# Core.net
KiCad netlist of a schematic drawn in Altium Designer
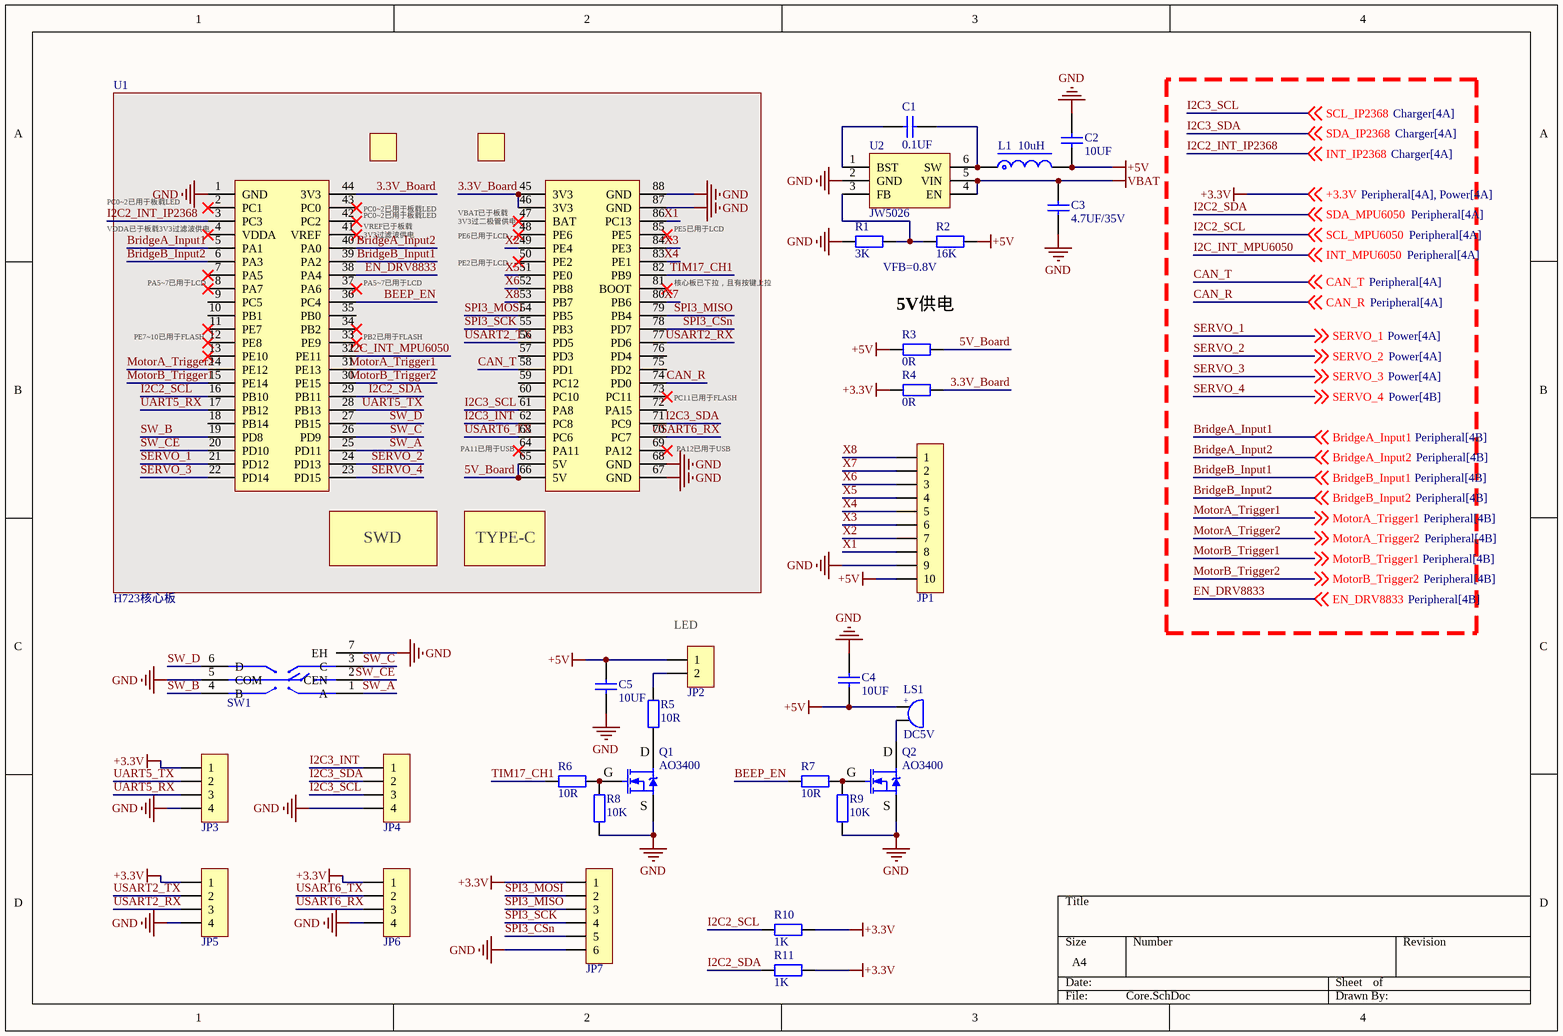
[diagram p0: Core.SchDoc]

(export (version "E")
  (design (tool "Eeschema 10.0.6"))
  (components
    (comp (ref "C1")
      (value "0.1UF")
      (footprint "C0402_NS")
      (description "贴片电容/MLCC电容")
      (libsource (lib "阻容") (part "C"))
    )
    (comp (ref "C2")
      (value "10UF")
      (footprint "C0805_NS")
      (description "贴片电容/MLCC电容")
      (libsource (lib "阻容") (part "C"))
    )
    (comp (ref "C3")
      (value "4.7UF/35V")
      (footprint "C0603_NS")
      (description "贴片电容/MLCC电容")
      (libsource (lib "阻容") (part "C"))
    )
    (comp (ref "C4")
      (value "10UF")
      (footprint "C0805_NS")
      (description "贴片电容/MLCC电容")
      (libsource (lib "阻容") (part "C"))
    )
    (comp (ref "C5")
      (value "10UF")
      (footprint "C0805_NS")
      (description "贴片电容/MLCC电容")
      (libsource (lib "阻容") (part "C"))
    )
    (comp (ref "JP1")
      (value "HDR-1X10")
      (footprint "HDR2.54-WI-10P")
      (description "10P接插件")
      (libsource (lib "2.54mm连接器") (part "Header 10"))
    )
    (comp (ref "JP2")
      (value "HDR-1X2")
      (footprint "XH2.54-WI-2P")
      (description "2P接插件")
      (libsource (lib "2.54mm连接器") (part "Header 2"))
    )
    (comp (ref "JP3")
      (value "HDR-1X4")
      (footprint "XH2.54-WI-4P")
      (description "4P接插件")
      (libsource (lib "2.54mm连接器") (part "Header 4"))
    )
    (comp (ref "JP4")
      (value "HDR-1X4")
      (footprint "XH2.54-WI-4P")
      (description "4P接插件")
      (libsource (lib "2.54mm连接器") (part "Header 4"))
    )
    (comp (ref "JP5")
      (value "HDR-1X4")
      (footprint "XH2.54-WI-4P")
      (description "4P接插件")
      (libsource (lib "2.54mm连接器") (part "Header 4"))
    )
    (comp (ref "JP6")
      (value "HDR-1X4")
      (footprint "HDR2.54-WI-4P")
      (description "4P接插件")
      (libsource (lib "2.54mm连接器") (part "Header 4"))
    )
    (comp (ref "JP7")
      (value "HDR-1X6")
      (footprint "HDR2.54-WI-6P")
      (description "6P接插件")
      (libsource (lib "2.54mm连接器") (part "Header 6"))
    )
    (comp (ref "L1")
      (value "10uH")
      (footprint "L-SMD-0420")
      (description "一体成型电感")
      (libsource (lib "电感") (part "L-Molding Choke"))
    )
    (comp (ref "LS1")
      (value "DC5V")
      (footprint "BEEP 5x9x5.5")
      (description "蜂鸣器")
      (libsource (lib "其他") (part "BEEP"))
    )
    (comp (ref "Q1")
      (value "AO3400")
      (footprint "SOT23-3_L2.9_W1.3_P0.95")
      (description "N沟道 30V/4.2A")
      (libsource (lib "三极管-MOS管") (part "AO3400"))
    )
    (comp (ref "Q2")
      (value "AO3400")
      (footprint "SOT23-3_L2.9_W1.3_P0.95")
      (description "N沟道 30V/4.2A")
      (libsource (lib "三极管-MOS管") (part "AO3400"))
    )
    (comp (ref "R1")
      (value "3K")
      (footprint "R0402_NS")
      (description "贴片电阻")
      (libsource (lib "阻容") (part "R"))
    )
    (comp (ref "R2")
      (value "16K")
      (footprint "R0402_NS")
      (description "贴片电阻")
      (libsource (lib "阻容") (part "R"))
    )
    (comp (ref "R3")
      (value "0R")
      (footprint "R0805_NS")
      (description "贴片电阻")
      (libsource (lib "阻容") (part "R"))
    )
    (comp (ref "R4")
      (value "0R")
      (footprint "R0805_NS")
      (description "贴片电阻")
      (libsource (lib "阻容") (part "R"))
    )
    (comp (ref "R5")
      (value "10R")
      (footprint "R0603_NS")
      (description "贴片电阻")
      (libsource (lib "阻容") (part "R"))
    )
    (comp (ref "R6")
      (value "10R")
      (footprint "R0603_NS")
      (description "贴片电阻")
      (libsource (lib "阻容") (part "R"))
    )
    (comp (ref "R7")
      (value "10R")
      (footprint "R0603_NS")
      (description "贴片电阻")
      (libsource (lib "阻容") (part "R"))
    )
    (comp (ref "R8")
      (value "10K")
      (footprint "R0603_NS")
      (description "贴片电阻")
      (libsource (lib "阻容") (part "R"))
    )
    (comp (ref "R9")
      (value "10K")
      (footprint "R0603_NS")
      (description "贴片电阻")
      (libsource (lib "阻容") (part "R"))
    )
    (comp (ref "R10")
      (value "1K")
      (footprint "R0402_NS")
      (description "贴片电阻")
      (libsource (lib "阻容") (part "R"))
    )
    (comp (ref "R11")
      (value "1K")
      (footprint "R0402_NS")
      (description "贴片电阻")
      (libsource (lib "阻容") (part "R"))
    )
    (comp (ref "SW1")
      (value "TM-4175-B-A")
      (footprint "SW-SMD_TM-4175-B-X")
      (description "五向开关")
      (libsource (lib "轻触开关") (part "TM-4175-B-A"))
    )
    (comp (ref "U1") (value "H723核心板") (footprint "H723核心板") (libsource (lib "Schlib1") (part "H723核心板")))
    (comp (ref "U2")
      (value "JW5026")
      (footprint "SOT23-6_L3.0_W1.7_P0.95")
      (description "40V/1A/1.1MHz同步降压转换器")
      (libsource (lib "电源IC") (part "JW5026"))
    )
  )
  (nets
    (net (code "1") (name "+3.3V") (class "Default")
      (node (ref "JP3") (pin "1") (pinfunction "1_1") (pintype "passive"))
      (node (ref "JP5") (pin "1") (pinfunction "1_1") (pintype "passive"))
      (node (ref "JP6") (pin "1") (pinfunction "1_1") (pintype "passive"))
      (node (ref "JP7") (pin "1") (pinfunction "1_1") (pintype "passive"))
      (node (ref "R10") (pin "2") (pinfunction "2_2") (pintype "passive"))
      (node (ref "R11") (pin "2") (pinfunction "2_2") (pintype "passive"))
      (node (ref "R4") (pin "1") (pinfunction "1_1") (pintype "passive"))
    )
    (net (code "2") (name "+5V") (class "Default")
      (node (ref "C2") (pin "2") (pinfunction "2_2") (pintype "passive"))
      (node (ref "C4") (pin "1") (pinfunction "1_1") (pintype "passive"))
      (node (ref "C5") (pin "2") (pinfunction "2_2") (pintype "passive"))
      (node (ref "JP1") (pin "10") (pinfunction "10_10") (pintype "passive"))
      (node (ref "JP2") (pin "1") (pinfunction "1_1") (pintype "passive"))
      (node (ref "L1") (pin "2") (pinfunction "2_2") (pintype "passive"))
      (node (ref "LS1") (pin "1") (pinfunction "1_1") (pintype "passive"))
      (node (ref "R2") (pin "1") (pinfunction "1_1") (pintype "passive"))
      (node (ref "R3") (pin "1") (pinfunction "1_1") (pintype "passive"))
    )
    (net (code "3") (name "/3.3V_Board") (class "Default")
      (node (ref "R4") (pin "2") (pinfunction "2_2") (pintype "passive"))
      (node (ref "U1") (pin "44") (pinfunction "3V3_44") (pintype "passive"))
      (node (ref "U1") (pin "45") (pinfunction "3V3_45") (pintype "passive"))
      (node (ref "U1") (pin "46") (pinfunction "3V3_46") (pintype "passive"))
    )
    (net (code "4") (name "/5V_Board") (class "Default")
      (node (ref "R3") (pin "2") (pinfunction "2_2") (pintype "passive"))
      (node (ref "U1") (pin "65") (pinfunction "5V_65") (pintype "passive"))
      (node (ref "U1") (pin "66") (pinfunction "5V_66") (pintype "passive"))
    )
    (net (code "5") (name "/BEEP_EN") (class "Default")
      (node (ref "R7") (pin "2") (pinfunction "2_2") (pintype "passive"))
      (node (ref "U1") (pin "36") (pinfunction "PC4_36") (pintype "passive"))
    )
    (net (code "6") (name "/I2C3_INT") (class "Default")
      (node (ref "JP4") (pin "1") (pinfunction "1_1") (pintype "passive"))
      (node (ref "U1") (pin "62") (pinfunction "PC8_62") (pintype "passive"))
    )
    (net (code "7") (name "/SPI3_CSn") (class "Default")
      (node (ref "JP7") (pin "5") (pinfunction "5_5") (pintype "passive"))
      (node (ref "U1") (pin "78") (pinfunction "PD7_78") (pintype "passive"))
    )
    (net (code "8") (name "/SPI3_MISO") (class "Default")
      (node (ref "JP7") (pin "3") (pinfunction "3_3") (pintype "passive"))
      (node (ref "U1") (pin "79") (pinfunction "PB4_79") (pintype "passive"))
    )
    (net (code "9") (name "/SPI3_MOSI") (class "Default")
      (node (ref "JP7") (pin "2") (pinfunction "2_2") (pintype "passive"))
      (node (ref "U1") (pin "54") (pinfunction "PB5_54") (pintype "passive"))
    )
    (net (code "10") (name "/SPI3_SCK") (class "Default")
      (node (ref "JP7") (pin "4") (pinfunction "4_4") (pintype "passive"))
      (node (ref "U1") (pin "55") (pinfunction "PB3_55") (pintype "passive"))
    )
    (net (code "11") (name "/SW_A") (class "Default")
      (node (ref "SW1") (pin "1") (pinfunction "A_1") (pintype "passive"))
      (node (ref "U1") (pin "25") (pinfunction "PD11_25") (pintype "passive"))
    )
    (net (code "12") (name "/SW_B") (class "Default")
      (node (ref "SW1") (pin "4") (pinfunction "B_4") (pintype "passive"))
      (node (ref "U1") (pin "19") (pinfunction "PD8_19") (pintype "passive"))
    )
    (net (code "13") (name "/SW_C") (class "Default")
      (node (ref "SW1") (pin "3") (pinfunction "C_3") (pintype "passive"))
      (node (ref "U1") (pin "26") (pinfunction "PD9_26") (pintype "passive"))
    )
    (net (code "14") (name "/SW_CE") (class "Default")
      (node (ref "SW1") (pin "2") (pinfunction "CEN_2") (pintype "passive"))
      (node (ref "U1") (pin "20") (pinfunction "PD10_20") (pintype "passive"))
    )
    (net (code "15") (name "/SW_D") (class "Default")
      (node (ref "SW1") (pin "6") (pinfunction "D_6") (pintype "passive"))
      (node (ref "U1") (pin "27") (pinfunction "PB15_27") (pintype "passive"))
    )
    (net (code "16") (name "/TIM17_CH1") (class "Default")
      (node (ref "R6") (pin "2") (pinfunction "2_2") (pintype "passive"))
      (node (ref "U1") (pin "82") (pinfunction "PB9_82") (pintype "passive"))
    )
    (net (code "17") (name "/UART5_RX") (class "Default")
      (node (ref "JP3") (pin "3") (pinfunction "3_3") (pintype "passive"))
      (node (ref "U1") (pin "17") (pinfunction "PB12_17") (pintype "passive"))
    )
    (net (code "18") (name "/UART5_TX") (class "Default")
      (node (ref "JP3") (pin "2") (pinfunction "2_2") (pintype "passive"))
      (node (ref "U1") (pin "28") (pinfunction "PB13_28") (pintype "passive"))
    )
    (net (code "19") (name "/USART2_RX") (class "Default")
      (node (ref "JP5") (pin "3") (pinfunction "3_3") (pintype "passive"))
      (node (ref "U1") (pin "77") (pinfunction "PD6_77") (pintype "passive"))
    )
    (net (code "20") (name "/USART2_TX") (class "Default")
      (node (ref "JP5") (pin "2") (pinfunction "2_2") (pintype "passive"))
      (node (ref "U1") (pin "56") (pinfunction "PD5_56") (pintype "passive"))
    )
    (net (code "21") (name "/USART6_RX") (class "Default")
      (node (ref "JP6") (pin "3") (pinfunction "3_3") (pintype "passive"))
      (node (ref "U1") (pin "70") (pinfunction "PC7_70") (pintype "passive"))
    )
    (net (code "22") (name "/USART6_TX") (class "Default")
      (node (ref "JP6") (pin "2") (pinfunction "2_2") (pintype "passive"))
      (node (ref "U1") (pin "63") (pinfunction "PC6_63") (pintype "passive"))
    )
    (net (code "23") (name "/X1") (class "Default")
      (node (ref "JP1") (pin "8") (pinfunction "8_8") (pintype "passive"))
      (node (ref "U1") (pin "86") (pinfunction "PC13_86") (pintype "passive"))
    )
    (net (code "24") (name "/X2") (class "Default")
      (node (ref "JP1") (pin "7") (pinfunction "7_7") (pintype "passive"))
      (node (ref "U1") (pin "49") (pinfunction "PE4_49") (pintype "passive"))
    )
    (net (code "25") (name "/X3") (class "Default")
      (node (ref "JP1") (pin "6") (pinfunction "6_6") (pintype "passive"))
      (node (ref "U1") (pin "84") (pinfunction "PE3_84") (pintype "passive"))
    )
    (net (code "26") (name "/X4") (class "Default")
      (node (ref "JP1") (pin "5") (pinfunction "5_5") (pintype "passive"))
      (node (ref "U1") (pin "83") (pinfunction "PE1_83") (pintype "passive"))
    )
    (net (code "27") (name "/X5") (class "Default")
      (node (ref "JP1") (pin "4") (pinfunction "4_4") (pintype "passive"))
      (node (ref "U1") (pin "51") (pinfunction "PE0_51") (pintype "passive"))
    )
    (net (code "28") (name "/X6") (class "Default")
      (node (ref "JP1") (pin "3") (pinfunction "3_3") (pintype "passive"))
      (node (ref "U1") (pin "52") (pinfunction "PB8_52") (pintype "passive"))
    )
    (net (code "29") (name "/X7") (class "Default")
      (node (ref "JP1") (pin "2") (pinfunction "2_2") (pintype "passive"))
      (node (ref "U1") (pin "80") (pinfunction "PB6_80") (pintype "passive"))
    )
    (net (code "30") (name "/X8") (class "Default")
      (node (ref "JP1") (pin "1") (pinfunction "1_1") (pintype "passive"))
      (node (ref "U1") (pin "53") (pinfunction "PB7_53") (pintype "passive"))
    )
    (net (code "31") (name "BridgeA_Input1") (class "Default")
      (node (ref "U1") (pin "5") (pinfunction "PA1_5") (pintype "passive"))
    )
    (net (code "32") (name "BridgeA_Input2") (class "Default")
      (node (ref "U1") (pin "40") (pinfunction "PA0_40") (pintype "passive"))
    )
    (net (code "33") (name "BridgeB_Input1") (class "Default")
      (node (ref "U1") (pin "39") (pinfunction "PA2_39") (pintype "passive"))
    )
    (net (code "34") (name "BridgeB_Input2") (class "Default")
      (node (ref "U1") (pin "6") (pinfunction "PA3_6") (pintype "passive"))
    )
    (net (code "35") (name "CAN_R") (class "Default")
      (node (ref "U1") (pin "74") (pinfunction "PD0_74") (pintype "passive"))
    )
    (net (code "36") (name "CAN_T") (class "Default")
      (node (ref "U1") (pin "58") (pinfunction "PD1_58") (pintype "passive"))
    )
    (net (code "37") (name "EN_DRV8833") (class "Default")
      (node (ref "U1") (pin "38") (pinfunction "PA4_38") (pintype "passive"))
    )
    (net (code "38") (name "GND") (class "Default")
      (node (ref "C2") (pin "1") (pinfunction "1_1") (pintype "passive"))
      (node (ref "C3") (pin "1") (pinfunction "1_1") (pintype "passive"))
      (node (ref "C4") (pin "2") (pinfunction "2_2") (pintype "passive"))
      (node (ref "C5") (pin "1") (pinfunction "1_1") (pintype "passive"))
      (node (ref "JP1") (pin "9") (pinfunction "9_9") (pintype "passive"))
      (node (ref "JP3") (pin "4") (pinfunction "4_4") (pintype "passive"))
      (node (ref "JP4") (pin "4") (pinfunction "4_4") (pintype "passive"))
      (node (ref "JP5") (pin "4") (pinfunction "4_4") (pintype "passive"))
      (node (ref "JP6") (pin "4") (pinfunction "4_4") (pintype "passive"))
      (node (ref "JP7") (pin "6") (pinfunction "6_6") (pintype "passive"))
      (node (ref "Q1") (pin "2") (pinfunction "S_2") (pintype "passive"))
      (node (ref "Q2") (pin "2") (pinfunction "S_2") (pintype "passive"))
      (node (ref "R1") (pin "2") (pinfunction "2_2") (pintype "passive"))
      (node (ref "R8") (pin "2") (pinfunction "2_2") (pintype "passive"))
      (node (ref "R9") (pin "2") (pinfunction "2_2") (pintype "passive"))
      (node (ref "SW1") (pin "5") (pinfunction "COM_5") (pintype "passive"))
      (node (ref "SW1") (pin "7") (pinfunction "EH_7") (pintype "passive"))
      (node (ref "U1") (pin "1") (pinfunction "GND_1") (pintype "passive"))
      (node (ref "U1") (pin "67") (pinfunction "GND_67") (pintype "passive"))
      (node (ref "U1") (pin "68") (pinfunction "GND_68") (pintype "passive"))
      (node (ref "U1") (pin "87") (pinfunction "GND_87") (pintype "passive"))
      (node (ref "U1") (pin "88") (pinfunction "GND_88") (pintype "passive"))
      (node (ref "U2") (pin "2") (pinfunction "GND_2") (pintype "passive"))
    )
    (net (code "39") (name "INT_IP2368") (class "Default")
      (node (ref "U1") (pin "3") (pinfunction "PC3_3") (pintype "passive"))
    )
    (net (code "40") (name "INT_MPU6050") (class "Default")
      (node (ref "U1") (pin "32") (pinfunction "PE11_32") (pintype "passive"))
    )
    (net (code "41") (name "MotorA_Trigger1") (class "Default")
      (node (ref "U1") (pin "31") (pinfunction "PE13_31") (pintype "passive"))
    )
    (net (code "42") (name "MotorA_Trigger2") (class "Default")
      (node (ref "U1") (pin "14") (pinfunction "PE12_14") (pintype "passive"))
    )
    (net (code "43") (name "MotorB_Trigger1") (class "Default")
      (node (ref "U1") (pin "15") (pinfunction "PE14_15") (pintype "passive"))
    )
    (net (code "44") (name "MotorB_Trigger2") (class "Default")
      (node (ref "U1") (pin "30") (pinfunction "PE15_30") (pintype "passive"))
    )
    (net (code "45") (name "Net-(JP2-Pad2)") (class "Default")
      (node (ref "JP2") (pin "2") (pinfunction "2_2") (pintype "passive"))
      (node (ref "R5") (pin "2") (pinfunction "2_2") (pintype "passive"))
    )
    (net (code "46") (name "Net-(Q1-D)") (class "Default")
      (node (ref "Q1") (pin "3") (pinfunction "D_3") (pintype "passive"))
      (node (ref "R5") (pin "1") (pinfunction "1_1") (pintype "passive"))
    )
    (net (code "47") (name "Net-(Q1-G)") (class "Default")
      (node (ref "Q1") (pin "1") (pinfunction "G_1") (pintype "passive"))
      (node (ref "R6") (pin "1") (pinfunction "1_1") (pintype "passive"))
      (node (ref "R8") (pin "1") (pinfunction "1_1") (pintype "passive"))
    )
    (net (code "48") (name "Net-(Q2-D)") (class "Default")
      (node (ref "LS1") (pin "2") (pinfunction "2_2") (pintype "passive"))
      (node (ref "Q2") (pin "3") (pinfunction "D_3") (pintype "passive"))
    )
    (net (code "49") (name "Net-(Q2-G)") (class "Default")
      (node (ref "Q2") (pin "1") (pinfunction "G_1") (pintype "passive"))
      (node (ref "R7") (pin "1") (pinfunction "1_1") (pintype "passive"))
      (node (ref "R9") (pin "1") (pinfunction "1_1") (pintype "passive"))
    )
    (net (code "50") (name "Net-(U2-BST)") (class "Default")
      (node (ref "C1") (pin "1") (pinfunction "1_1") (pintype "passive"))
      (node (ref "U2") (pin "1") (pinfunction "BST_1") (pintype "passive"))
    )
    (net (code "51") (name "Net-(U2-FB)") (class "Default")
      (node (ref "R1") (pin "1") (pinfunction "1_1") (pintype "passive"))
      (node (ref "R2") (pin "2") (pinfunction "2_2") (pintype "passive"))
      (node (ref "U2") (pin "3") (pinfunction "FB_3") (pintype "passive"))
    )
    (net (code "52") (name "Net-(U2-SW)") (class "Default")
      (node (ref "C1") (pin "2") (pinfunction "2_2") (pintype "passive"))
      (node (ref "L1") (pin "1") (pinfunction "1_1") (pintype "passive"))
      (node (ref "U2") (pin "6") (pinfunction "SW_6") (pintype "passive"))
    )
    (net (code "53") (name "SCL_IP2368") (class "Default")
      (node (ref "JP4") (pin "3") (pinfunction "3_3") (pintype "passive"))
      (node (ref "U1") (pin "61") (pinfunction "PA8_61") (pintype "passive"))
    )
    (net (code "54") (name "SCL_MPU6050") (class "Default")
      (node (ref "R10") (pin "1") (pinfunction "1_1") (pintype "passive"))
      (node (ref "U1") (pin "16") (pinfunction "PB10_16") (pintype "passive"))
    )
    (net (code "55") (name "SDA_IP2368") (class "Default")
      (node (ref "JP4") (pin "2") (pinfunction "2_2") (pintype "passive"))
      (node (ref "U1") (pin "71") (pinfunction "PC9_71") (pintype "passive"))
    )
    (net (code "56") (name "SDA_MPU6050") (class "Default")
      (node (ref "R11") (pin "1") (pinfunction "1_1") (pintype "passive"))
      (node (ref "U1") (pin "29") (pinfunction "PB11_29") (pintype "passive"))
    )
    (net (code "57") (name "SERVO_1") (class "Default")
      (node (ref "U1") (pin "21") (pinfunction "PD12_21") (pintype "passive"))
    )
    (net (code "58") (name "SERVO_2") (class "Default")
      (node (ref "U1") (pin "24") (pinfunction "PD13_24") (pintype "passive"))
    )
    (net (code "59") (name "SERVO_3") (class "Default")
      (node (ref "U1") (pin "22") (pinfunction "PD14_22") (pintype "passive"))
    )
    (net (code "60") (name "SERVO_4") (class "Default")
      (node (ref "U1") (pin "23") (pinfunction "PD15_23") (pintype "passive"))
    )
    (net (code "61") (name "VBAT") (class "Default")
      (node (ref "C3") (pin "2") (pinfunction "2_2") (pintype "passive"))
      (node (ref "U2") (pin "4") (pinfunction "EN_4") (pintype "passive"))
      (node (ref "U2") (pin "5") (pinfunction "VIN_5") (pintype "passive"))
    )
    (net (code "62") (name "unconnected-(U1-BAT-Pad47)") (class "Default")
      (node (ref "U1") (pin "47") (pinfunction "BAT_47") (pintype "passive+no_connect"))
    )
    (net (code "63") (name "unconnected-(U1-BOOT-Pad81)") (class "Default")
      (node (ref "U1") (pin "81") (pinfunction "BOOT_81") (pintype "passive+no_connect"))
    )
    (net (code "64") (name "unconnected-(U1-PA5-Pad7)") (class "Default")
      (node (ref "U1") (pin "7") (pinfunction "PA5_7") (pintype "passive+no_connect"))
    )
    (net (code "65") (name "unconnected-(U1-PA6-Pad37)") (class "Default")
      (node (ref "U1") (pin "37") (pinfunction "PA6_37") (pintype "passive+no_connect"))
    )
    (net (code "66") (name "unconnected-(U1-PA7-Pad8)") (class "Default")
      (node (ref "U1") (pin "8") (pinfunction "PA7_8") (pintype "passive+no_connect"))
    )
    (net (code "67") (name "unconnected-(U1-PA11-Pad64)") (class "Default")
      (node (ref "U1") (pin "64") (pinfunction "PA11_64") (pintype "passive+no_connect"))
    )
    (net (code "68") (name "unconnected-(U1-PA12-Pad69)") (class "Default")
      (node (ref "U1") (pin "69") (pinfunction "PA12_69") (pintype "passive+no_connect"))
    )
    (net (code "69") (name "unconnected-(U1-PA15-Pad72)") (class "Default")
      (node (ref "U1") (pin "72") (pinfunction "PA15_72") (pintype "passive"))
    )
    (net (code "70") (name "unconnected-(U1-PB0-Pad35)") (class "Default")
      (node (ref "U1") (pin "35") (pinfunction "PB0_35") (pintype "passive"))
    )
    (net (code "71") (name "unconnected-(U1-PB1-Pad10)") (class "Default")
      (node (ref "U1") (pin "10") (pinfunction "PB1_10") (pintype "passive"))
    )
    (net (code "72") (name "unconnected-(U1-PB2-Pad34)") (class "Default")
      (node (ref "U1") (pin "34") (pinfunction "PB2_34") (pintype "passive+no_connect"))
    )
    (net (code "73") (name "unconnected-(U1-PB14-Pad18)") (class "Default")
      (node (ref "U1") (pin "18") (pinfunction "PB14_18") (pintype "passive"))
    )
    (net (code "74") (name "unconnected-(U1-PC0-Pad43)") (class "Default")
      (node (ref "U1") (pin "43") (pinfunction "PC0_43") (pintype "passive+no_connect"))
    )
    (net (code "75") (name "unconnected-(U1-PC1-Pad2)") (class "Default")
      (node (ref "U1") (pin "2") (pinfunction "PC1_2") (pintype "passive+no_connect"))
    )
    (net (code "76") (name "unconnected-(U1-PC2-Pad42)") (class "Default")
      (node (ref "U1") (pin "42") (pinfunction "PC2_42") (pintype "passive+no_connect"))
    )
    (net (code "77") (name "unconnected-(U1-PC5-Pad9)") (class "Default")
      (node (ref "U1") (pin "9") (pinfunction "PC5_9") (pintype "passive"))
    )
    (net (code "78") (name "unconnected-(U1-PC10-Pad60)") (class "Default")
      (node (ref "U1") (pin "60") (pinfunction "PC10_60") (pintype "passive"))
    )
    (net (code "79") (name "unconnected-(U1-PC11-Pad73)") (class "Default")
      (node (ref "U1") (pin "73") (pinfunction "PC11_73") (pintype "passive+no_connect"))
    )
    (net (code "80") (name "unconnected-(U1-PC12-Pad59)") (class "Default")
      (node (ref "U1") (pin "59") (pinfunction "PC12_59") (pintype "passive"))
    )
    (net (code "81") (name "unconnected-(U1-PD2-Pad75)") (class "Default")
      (node (ref "U1") (pin "75") (pinfunction "PD2_75") (pintype "passive"))
    )
    (net (code "82") (name "unconnected-(U1-PD3-Pad57)") (class "Default")
      (node (ref "U1") (pin "57") (pinfunction "PD3_57") (pintype "passive"))
    )
    (net (code "83") (name "unconnected-(U1-PD4-Pad76)") (class "Default")
      (node (ref "U1") (pin "76") (pinfunction "PD4_76") (pintype "passive"))
    )
    (net (code "84") (name "unconnected-(U1-PE2-Pad50)") (class "Default")
      (node (ref "U1") (pin "50") (pinfunction "PE2_50") (pintype "passive+no_connect"))
    )
    (net (code "85") (name "unconnected-(U1-PE5-Pad85)") (class "Default")
      (node (ref "U1") (pin "85") (pinfunction "PE5_85") (pintype "passive+no_connect"))
    )
    (net (code "86") (name "unconnected-(U1-PE6-Pad48)") (class "Default")
      (node (ref "U1") (pin "48") (pinfunction "PE6_48") (pintype "passive+no_connect"))
    )
    (net (code "87") (name "unconnected-(U1-PE7-Pad11)") (class "Default")
      (node (ref "U1") (pin "11") (pinfunction "PE7_11") (pintype "passive+no_connect"))
    )
    (net (code "88") (name "unconnected-(U1-PE8-Pad12)") (class "Default")
      (node (ref "U1") (pin "12") (pinfunction "PE8_12") (pintype "passive+no_connect"))
    )
    (net (code "89") (name "unconnected-(U1-PE9-Pad33)") (class "Default")
      (node (ref "U1") (pin "33") (pinfunction "PE9_33") (pintype "passive+no_connect"))
    )
    (net (code "90") (name "unconnected-(U1-PE10-Pad13)") (class "Default")
      (node (ref "U1") (pin "13") (pinfunction "PE10_13") (pintype "passive+no_connect"))
    )
    (net (code "91") (name "unconnected-(U1-VDDA-Pad4)") (class "Default")
      (node (ref "U1") (pin "4") (pinfunction "VDDA_4") (pintype "passive+no_connect"))
    )
    (net (code "92") (name "unconnected-(U1-VREF-Pad41)") (class "Default")
      (node (ref "U1") (pin "41") (pinfunction "VREF_41") (pintype "passive+no_connect"))
    )
  )
)
